# untitled.net
KiCad netlist of a schematic drawn in EAGLE
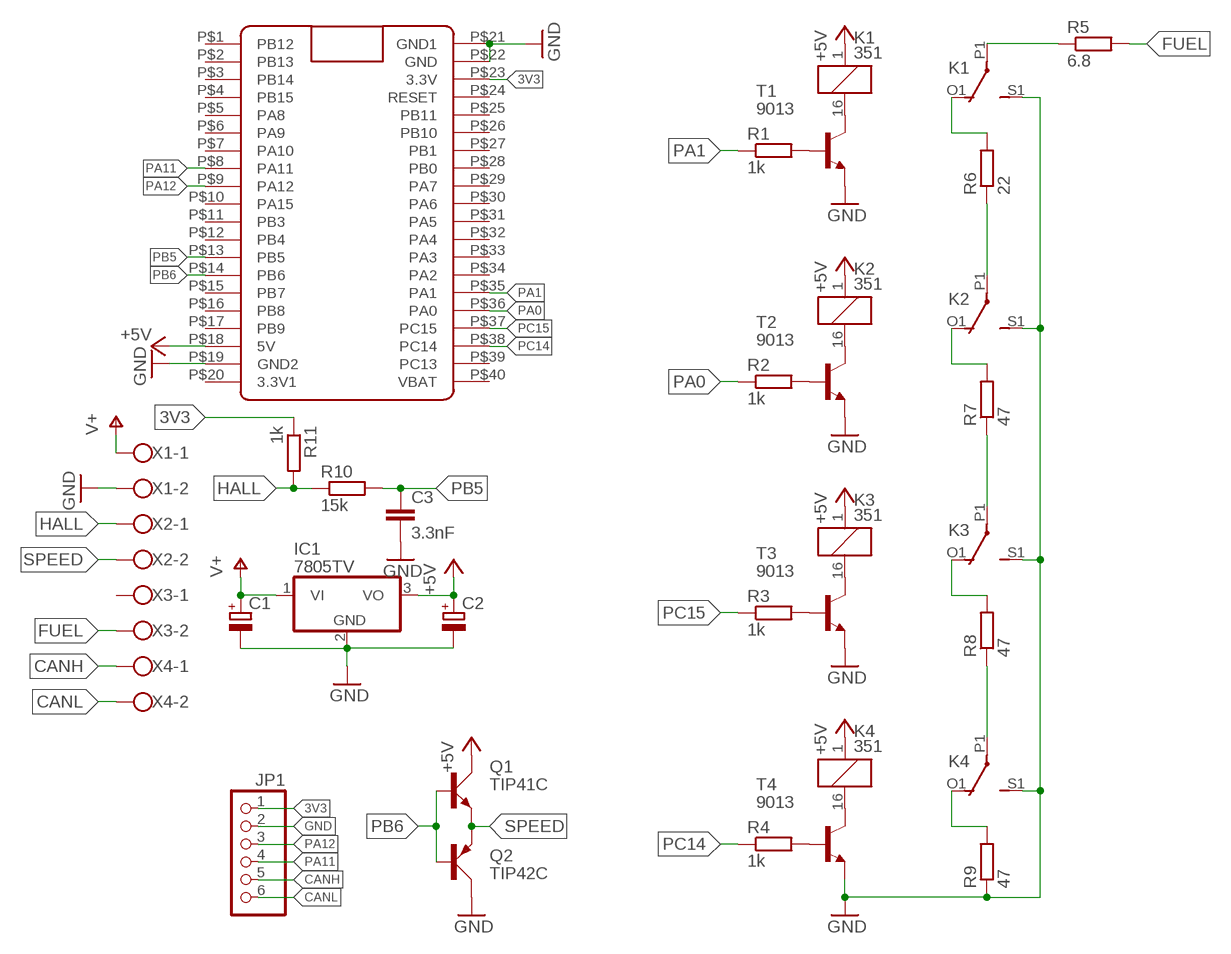
[diagram p0: schematic, sheet 1]

(export (version "E")
  (design (tool "Eeschema 10.0.6"))
  (components
    (comp (ref "C1")
      (value "CPOL-EUE5-10.5")
      (footprint "eagle-import:E5-10,5")
      (libsource (lib "eagle-import") (part "CPOL-EUE5-10.5"))
    )
    (comp (ref "C2")
      (value "CPOL-EUE5-10.5")
      (footprint "eagle-import:E5-10,5")
      (libsource (lib "eagle-import") (part "CPOL-EUE5-10.5"))
    )
    (comp (ref "C3")
      (value "3.3nF")
      (footprint "eagle-import:C050-024X044")
      (libsource (lib "eagle-import") (part "C-EU050-024X044"))
    )
    (comp (ref "IC1")
      (value "7805TV")
      (footprint "eagle-import:TO220V")
      (libsource (lib "eagle-import") (part "78TV05"))
    )
    (comp (ref "JP1")
      (value "PINHD-1X6")
      (footprint "eagle-import:1X06")
      (libsource (lib "eagle-import") (part "PINHD-1X6"))
    )
    (comp (ref "K1")
      (value "351")
      (footprint "eagle-import:351")
      (libsource (lib "eagle-import") (part "351"))
    )
    (comp (ref "K2")
      (value "351")
      (footprint "eagle-import:351")
      (libsource (lib "eagle-import") (part "351"))
    )
    (comp (ref "K3")
      (value "351")
      (footprint "eagle-import:351")
      (libsource (lib "eagle-import") (part "351"))
    )
    (comp (ref "K4")
      (value "351")
      (footprint "eagle-import:351")
      (libsource (lib "eagle-import") (part "351"))
    )
    (comp (ref "Q1")
      (value "TIP41C")
      (footprint "eagle-import:TO220AV")
      (libsource (lib "eagle-import") (part "TIP41C"))
    )
    (comp (ref "Q2")
      (value "TIP42C")
      (footprint "eagle-import:TO220AV")
      (libsource (lib "eagle-import") (part "TIP42C"))
    )
    (comp (ref "R1")
      (value "1k")
      (footprint "eagle-import:0207_7")
      (libsource (lib "eagle-import") (part "R-EU_0207/7"))
    )
    (comp (ref "R2")
      (value "1k")
      (footprint "eagle-import:0207_7")
      (libsource (lib "eagle-import") (part "R-EU_0207/7"))
    )
    (comp (ref "R3")
      (value "1k")
      (footprint "eagle-import:0207_7")
      (libsource (lib "eagle-import") (part "R-EU_0207/7"))
    )
    (comp (ref "R4")
      (value "1k")
      (footprint "eagle-import:0207_7")
      (libsource (lib "eagle-import") (part "R-EU_0207/7"))
    )
    (comp (ref "R5")
      (value "6.8")
      (footprint "eagle-import:0207_7")
      (libsource (lib "eagle-import") (part "R-EU_0207/7"))
    )
    (comp (ref "R6")
      (value "22")
      (footprint "eagle-import:0207_7")
      (libsource (lib "eagle-import") (part "R-EU_0207/7"))
    )
    (comp (ref "R7")
      (value "47")
      (footprint "eagle-import:0207_7")
      (libsource (lib "eagle-import") (part "R-EU_0207/7"))
    )
    (comp (ref "R8")
      (value "47")
      (footprint "eagle-import:0207_7")
      (libsource (lib "eagle-import") (part "R-EU_0207/7"))
    )
    (comp (ref "R9")
      (value "47")
      (footprint "eagle-import:0207_7")
      (libsource (lib "eagle-import") (part "R-EU_0207/7"))
    )
    (comp (ref "R10")
      (value "15k")
      (footprint "eagle-import:0207_7")
      (libsource (lib "eagle-import") (part "R-EU_0207/7"))
    )
    (comp (ref "R11")
      (value "1k")
      (footprint "eagle-import:0207_7")
      (libsource (lib "eagle-import") (part "R-EU_0207/7"))
    )
    (comp (ref "T1")
      (value "9013")
      (footprint "eagle-import:TO92-EBC")
      (libsource (lib "eagle-import") (part "-NPN-TO92-EBC"))
    )
    (comp (ref "T2")
      (value "9013")
      (footprint "eagle-import:TO92-EBC")
      (libsource (lib "eagle-import") (part "-NPN-TO92-EBC"))
    )
    (comp (ref "T3")
      (value "9013")
      (footprint "eagle-import:TO92-EBC")
      (libsource (lib "eagle-import") (part "-NPN-TO92-EBC"))
    )
    (comp (ref "T4")
      (value "9013")
      (footprint "eagle-import:TO92-EBC")
      (libsource (lib "eagle-import") (part "-NPN-TO92-EBC"))
    )
    (comp (ref "U$1")
      (value "BLUE_PILL")
      (footprint "eagle-import:BLUE_PILL")
      (libsource (lib "eagle-import") (part "BLUE_PILL"))
    )
    (comp (ref "X1")
      (value "W237-102")
      (footprint "eagle-import:W237-102")
      (fields (field (name "MPN") "237-102"))
      (libsource (lib "eagle-import") (part "W237-102"))
    )
    (comp (ref "X2")
      (value "W237-102")
      (footprint "eagle-import:W237-102")
      (fields (field (name "MPN") "237-102"))
      (libsource (lib "eagle-import") (part "W237-102"))
    )
    (comp (ref "X3")
      (value "W237-102")
      (footprint "eagle-import:W237-102")
      (fields (field (name "MPN") "237-102"))
      (libsource (lib "eagle-import") (part "W237-102"))
    )
    (comp (ref "X4")
      (value "W237-102")
      (footprint "eagle-import:W237-102")
      (fields (field (name "MPN") "237-102"))
      (libsource (lib "eagle-import") (part "W237-102"))
    )
  )
  (nets
    (net (code "1") (name "+5V") (class "Default")
      (node (ref "C2") (pin "+") (pinfunction "+_+") (pintype "passive"))
      (node (ref "IC1") (pin "3") (pinfunction "VO_3") (pintype "passive"))
      (node (ref "K1") (pin "1") (pinfunction "1_1") (pintype "passive"))
      (node (ref "K2") (pin "1") (pinfunction "1_1") (pintype "passive"))
      (node (ref "K3") (pin "1") (pinfunction "1_1") (pintype "passive"))
      (node (ref "K4") (pin "1") (pinfunction "1_1") (pintype "passive"))
      (node (ref "Q1") (pin "C") (pinfunction "C_C") (pintype "passive"))
      (node (ref "U$1") (pin "P$18") (pinfunction "5V_P$18") (pintype "bidirectional"))
    )
    (net (code "2") (name "3V3") (class "Default")
      (node (ref "JP1") (pin "1") (pinfunction "1_1") (pintype "passive"))
      (node (ref "R11") (pin "1") (pinfunction "1_1") (pintype "passive"))
      (node (ref "U$1") (pin "P$23") (pinfunction "3.3V_P$23") (pintype "bidirectional"))
    )
    (net (code "3") (name "CANH") (class "Default")
      (node (ref "JP1") (pin "5") (pinfunction "5_5") (pintype "passive"))
      (node (ref "X4") (pin "1") (pinfunction "KL_1") (pintype "passive"))
    )
    (net (code "4") (name "CANL") (class "Default")
      (node (ref "JP1") (pin "6") (pinfunction "6_6") (pintype "passive"))
      (node (ref "X4") (pin "2") (pinfunction "KL_2") (pintype "passive"))
    )
    (net (code "5") (name "FUEL") (class "Default")
      (node (ref "R5") (pin "2") (pinfunction "2_2") (pintype "passive"))
      (node (ref "X3") (pin "2") (pinfunction "KL_2") (pintype "passive"))
    )
    (net (code "6") (name "GND") (class "Default")
      (node (ref "C1") (pin "-") (pinfunction "-_-") (pintype "passive"))
      (node (ref "C2") (pin "-") (pinfunction "-_-") (pintype "passive"))
      (node (ref "C3") (pin "2") (pinfunction "2_2") (pintype "passive"))
      (node (ref "IC1") (pin "2") (pinfunction "GND_2") (pintype "passive"))
      (node (ref "JP1") (pin "2") (pinfunction "2_2") (pintype "passive"))
      (node (ref "K1") (pin "S1") (pinfunction "S_S1") (pintype "passive"))
      (node (ref "K2") (pin "S1") (pinfunction "S_S1") (pintype "passive"))
      (node (ref "K3") (pin "S1") (pinfunction "S_S1") (pintype "passive"))
      (node (ref "K4") (pin "S1") (pinfunction "S_S1") (pintype "passive"))
      (node (ref "Q2") (pin "C") (pinfunction "C_C") (pintype "passive"))
      (node (ref "R9") (pin "1") (pinfunction "1_1") (pintype "passive"))
      (node (ref "T1") (pin "E") (pinfunction "E_E") (pintype "passive"))
      (node (ref "T2") (pin "E") (pinfunction "E_E") (pintype "passive"))
      (node (ref "T3") (pin "E") (pinfunction "E_E") (pintype "passive"))
      (node (ref "T4") (pin "E") (pinfunction "E_E") (pintype "passive"))
      (node (ref "U$1") (pin "P$19") (pinfunction "GND2_P$19") (pintype "bidirectional"))
      (node (ref "U$1") (pin "P$21") (pinfunction "GND1_P$21") (pintype "power_in"))
      (node (ref "U$1") (pin "P$22") (pinfunction "GND_P$22") (pintype "bidirectional"))
      (node (ref "X1") (pin "2") (pinfunction "KL_2") (pintype "passive"))
    )
    (net (code "7") (name "HALL") (class "Default")
      (node (ref "R10") (pin "1") (pinfunction "1_1") (pintype "passive"))
      (node (ref "R11") (pin "2") (pinfunction "2_2") (pintype "passive"))
      (node (ref "X2") (pin "1") (pinfunction "KL_1") (pintype "passive"))
    )
    (net (code "8") (name "Net-(K1A-2)") (class "Default")
      (node (ref "K1") (pin "16") (pinfunction "2_16") (pintype "passive"))
      (node (ref "T1") (pin "C") (pinfunction "C_C") (pintype "passive"))
    )
    (net (code "9") (name "Net-(K1B-O)") (class "Default")
      (node (ref "K1") (pin "O1") (pinfunction "O_O1") (pintype "passive"))
      (node (ref "R6") (pin "2") (pinfunction "2_2") (pintype "passive"))
    )
    (net (code "10") (name "Net-(K1B-P)") (class "Default")
      (node (ref "K1") (pin "P1") (pinfunction "P_P1") (pintype "passive"))
      (node (ref "R5") (pin "1") (pinfunction "1_1") (pintype "passive"))
    )
    (net (code "11") (name "Net-(K2A-2)") (class "Default")
      (node (ref "K2") (pin "16") (pinfunction "2_16") (pintype "passive"))
      (node (ref "T2") (pin "C") (pinfunction "C_C") (pintype "passive"))
    )
    (net (code "12") (name "Net-(K2B-O)") (class "Default")
      (node (ref "K2") (pin "O1") (pinfunction "O_O1") (pintype "passive"))
      (node (ref "R7") (pin "2") (pinfunction "2_2") (pintype "passive"))
    )
    (net (code "13") (name "Net-(K2B-P)") (class "Default")
      (node (ref "K2") (pin "P1") (pinfunction "P_P1") (pintype "passive"))
      (node (ref "R6") (pin "1") (pinfunction "1_1") (pintype "passive"))
    )
    (net (code "14") (name "Net-(K3A-2)") (class "Default")
      (node (ref "K3") (pin "16") (pinfunction "2_16") (pintype "passive"))
      (node (ref "T3") (pin "C") (pinfunction "C_C") (pintype "passive"))
    )
    (net (code "15") (name "Net-(K3B-O)") (class "Default")
      (node (ref "K3") (pin "O1") (pinfunction "O_O1") (pintype "passive"))
      (node (ref "R8") (pin "2") (pinfunction "2_2") (pintype "passive"))
    )
    (net (code "16") (name "Net-(K3B-P)") (class "Default")
      (node (ref "K3") (pin "P1") (pinfunction "P_P1") (pintype "passive"))
      (node (ref "R7") (pin "1") (pinfunction "1_1") (pintype "passive"))
    )
    (net (code "17") (name "Net-(K4A-2)") (class "Default")
      (node (ref "K4") (pin "16") (pinfunction "2_16") (pintype "passive"))
      (node (ref "T4") (pin "C") (pinfunction "C_C") (pintype "passive"))
    )
    (net (code "18") (name "Net-(K4B-O)") (class "Default")
      (node (ref "K4") (pin "O1") (pinfunction "O_O1") (pintype "passive"))
      (node (ref "R9") (pin "2") (pinfunction "2_2") (pintype "passive"))
    )
    (net (code "19") (name "Net-(K4B-P)") (class "Default")
      (node (ref "K4") (pin "P1") (pinfunction "P_P1") (pintype "passive"))
      (node (ref "R8") (pin "1") (pinfunction "1_1") (pintype "passive"))
    )
    (net (code "20") (name "Net-(R1-Pad2)") (class "Default")
      (node (ref "R1") (pin "2") (pinfunction "2_2") (pintype "passive"))
      (node (ref "T1") (pin "B") (pinfunction "B_B") (pintype "passive"))
    )
    (net (code "21") (name "Net-(R2-Pad2)") (class "Default")
      (node (ref "R2") (pin "2") (pinfunction "2_2") (pintype "passive"))
      (node (ref "T2") (pin "B") (pinfunction "B_B") (pintype "passive"))
    )
    (net (code "22") (name "Net-(R3-Pad2)") (class "Default")
      (node (ref "R3") (pin "2") (pinfunction "2_2") (pintype "passive"))
      (node (ref "T3") (pin "B") (pinfunction "B_B") (pintype "passive"))
    )
    (net (code "23") (name "Net-(R4-Pad2)") (class "Default")
      (node (ref "R4") (pin "2") (pinfunction "2_2") (pintype "passive"))
      (node (ref "T4") (pin "B") (pinfunction "B_B") (pintype "passive"))
    )
    (net (code "24") (name "PA0") (class "Default")
      (node (ref "R2") (pin "1") (pinfunction "1_1") (pintype "passive"))
      (node (ref "U$1") (pin "P$36") (pinfunction "PA0_P$36") (pintype "bidirectional"))
    )
    (net (code "25") (name "PA1") (class "Default")
      (node (ref "R1") (pin "1") (pinfunction "1_1") (pintype "passive"))
      (node (ref "U$1") (pin "P$35") (pinfunction "PA1_P$35") (pintype "bidirectional"))
    )
    (net (code "26") (name "PA11") (class "Default")
      (node (ref "JP1") (pin "4") (pinfunction "4_4") (pintype "passive"))
      (node (ref "U$1") (pin "P$8") (pinfunction "PA11_P$8") (pintype "bidirectional"))
    )
    (net (code "27") (name "PA12") (class "Default")
      (node (ref "JP1") (pin "3") (pinfunction "3_3") (pintype "passive"))
      (node (ref "U$1") (pin "P$9") (pinfunction "PA12_P$9") (pintype "bidirectional"))
    )
    (net (code "28") (name "PB5") (class "Default")
      (node (ref "C3") (pin "1") (pinfunction "1_1") (pintype "passive"))
      (node (ref "R10") (pin "2") (pinfunction "2_2") (pintype "passive"))
      (node (ref "U$1") (pin "P$13") (pinfunction "PB5_P$13") (pintype "bidirectional"))
    )
    (net (code "29") (name "PB6") (class "Default")
      (node (ref "Q1") (pin "B") (pinfunction "B_B") (pintype "passive"))
      (node (ref "Q2") (pin "B") (pinfunction "B_B") (pintype "passive"))
      (node (ref "U$1") (pin "P$14") (pinfunction "PB6_P$14") (pintype "bidirectional"))
    )
    (net (code "30") (name "PC14") (class "Default")
      (node (ref "R4") (pin "1") (pinfunction "1_1") (pintype "passive"))
      (node (ref "U$1") (pin "P$38") (pinfunction "PC14_P$38") (pintype "bidirectional"))
    )
    (net (code "31") (name "PC15") (class "Default")
      (node (ref "R3") (pin "1") (pinfunction "1_1") (pintype "passive"))
      (node (ref "U$1") (pin "P$37") (pinfunction "PC15_P$37") (pintype "bidirectional"))
    )
    (net (code "32") (name "SPEED") (class "Default")
      (node (ref "Q1") (pin "E") (pinfunction "E_E") (pintype "passive"))
      (node (ref "Q2") (pin "E") (pinfunction "E_E") (pintype "passive"))
      (node (ref "X2") (pin "2") (pinfunction "KL_2") (pintype "passive"))
    )
    (net (code "33") (name "V+") (class "Default")
      (node (ref "C1") (pin "+") (pinfunction "+_+") (pintype "passive"))
      (node (ref "IC1") (pin "1") (pinfunction "VI_1") (pintype "input"))
      (node (ref "X1") (pin "1") (pinfunction "KL_1") (pintype "passive"))
    )
    (net (code "34") (name "unconnected-(U$1-3.3V1-PadP$20)") (class "Default")
      (node (ref "U$1") (pin "P$20") (pinfunction "3.3V1_P$20") (pintype "bidirectional"))
    )
    (net (code "35") (name "unconnected-(U$1-PA2-PadP$34)") (class "Default")
      (node (ref "U$1") (pin "P$34") (pinfunction "PA2_P$34") (pintype "bidirectional"))
    )
    (net (code "36") (name "unconnected-(U$1-PA3-PadP$33)") (class "Default")
      (node (ref "U$1") (pin "P$33") (pinfunction "PA3_P$33") (pintype "bidirectional"))
    )
    (net (code "37") (name "unconnected-(U$1-PA4-PadP$32)") (class "Default")
      (node (ref "U$1") (pin "P$32") (pinfunction "PA4_P$32") (pintype "bidirectional"))
    )
    (net (code "38") (name "unconnected-(U$1-PA5-PadP$31)") (class "Default")
      (node (ref "U$1") (pin "P$31") (pinfunction "PA5_P$31") (pintype "bidirectional"))
    )
    (net (code "39") (name "unconnected-(U$1-PA6-PadP$30)") (class "Default")
      (node (ref "U$1") (pin "P$30") (pinfunction "PA6_P$30") (pintype "bidirectional"))
    )
    (net (code "40") (name "unconnected-(U$1-PA7-PadP$29)") (class "Default")
      (node (ref "U$1") (pin "P$29") (pinfunction "PA7_P$29") (pintype "bidirectional"))
    )
    (net (code "41") (name "unconnected-(U$1-PA8-PadP$5)") (class "Default")
      (node (ref "U$1") (pin "P$5") (pinfunction "PA8_P$5") (pintype "bidirectional"))
    )
    (net (code "42") (name "unconnected-(U$1-PA9-PadP$6)") (class "Default")
      (node (ref "U$1") (pin "P$6") (pinfunction "PA9_P$6") (pintype "bidirectional"))
    )
    (net (code "43") (name "unconnected-(U$1-PA10-PadP$7)") (class "Default")
      (node (ref "U$1") (pin "P$7") (pinfunction "PA10_P$7") (pintype "bidirectional"))
    )
    (net (code "44") (name "unconnected-(U$1-PA15-PadP$10)") (class "Default")
      (node (ref "U$1") (pin "P$10") (pinfunction "PA15_P$10") (pintype "bidirectional"))
    )
    (net (code "45") (name "unconnected-(U$1-PB0-PadP$28)") (class "Default")
      (node (ref "U$1") (pin "P$28") (pinfunction "PB0_P$28") (pintype "bidirectional"))
    )
    (net (code "46") (name "unconnected-(U$1-PB1-PadP$27)") (class "Default")
      (node (ref "U$1") (pin "P$27") (pinfunction "PB1_P$27") (pintype "bidirectional"))
    )
    (net (code "47") (name "unconnected-(U$1-PB3-PadP$11)") (class "Default")
      (node (ref "U$1") (pin "P$11") (pinfunction "PB3_P$11") (pintype "bidirectional"))
    )
    (net (code "48") (name "unconnected-(U$1-PB4-PadP$12)") (class "Default")
      (node (ref "U$1") (pin "P$12") (pinfunction "PB4_P$12") (pintype "bidirectional"))
    )
    (net (code "49") (name "unconnected-(U$1-PB7-PadP$15)") (class "Default")
      (node (ref "U$1") (pin "P$15") (pinfunction "PB7_P$15") (pintype "bidirectional"))
    )
    (net (code "50") (name "unconnected-(U$1-PB8-PadP$16)") (class "Default")
      (node (ref "U$1") (pin "P$16") (pinfunction "PB8_P$16") (pintype "bidirectional"))
    )
    (net (code "51") (name "unconnected-(U$1-PB9-PadP$17)") (class "Default")
      (node (ref "U$1") (pin "P$17") (pinfunction "PB9_P$17") (pintype "bidirectional"))
    )
    (net (code "52") (name "unconnected-(U$1-PB10-PadP$26)") (class "Default")
      (node (ref "U$1") (pin "P$26") (pinfunction "PB10_P$26") (pintype "bidirectional"))
    )
    (net (code "53") (name "unconnected-(U$1-PB11-PadP$25)") (class "Default")
      (node (ref "U$1") (pin "P$25") (pinfunction "PB11_P$25") (pintype "bidirectional"))
    )
    (net (code "54") (name "unconnected-(U$1-PB12-PadP$1)") (class "Default")
      (node (ref "U$1") (pin "P$1") (pinfunction "PB12_P$1") (pintype "bidirectional"))
    )
    (net (code "55") (name "unconnected-(U$1-PB13-PadP$2)") (class "Default")
      (node (ref "U$1") (pin "P$2") (pinfunction "PB13_P$2") (pintype "bidirectional"))
    )
    (net (code "56") (name "unconnected-(U$1-PB14-PadP$3)") (class "Default")
      (node (ref "U$1") (pin "P$3") (pinfunction "PB14_P$3") (pintype "bidirectional"))
    )
    (net (code "57") (name "unconnected-(U$1-PB15-PadP$4)") (class "Default")
      (node (ref "U$1") (pin "P$4") (pinfunction "PB15_P$4") (pintype "bidirectional"))
    )
    (net (code "58") (name "unconnected-(U$1-PC13-PadP$39)") (class "Default")
      (node (ref "U$1") (pin "P$39") (pinfunction "PC13_P$39") (pintype "bidirectional"))
    )
    (net (code "59") (name "unconnected-(U$1-RESET-PadP$24)") (class "Default")
      (node (ref "U$1") (pin "P$24") (pinfunction "RESET_P$24") (pintype "bidirectional"))
    )
    (net (code "60") (name "unconnected-(U$1-VBAT-PadP$40)") (class "Default")
      (node (ref "U$1") (pin "P$40") (pinfunction "VBAT_P$40") (pintype "bidirectional"))
    )
    (net (code "61") (name "unconnected-(X3A-KL-Pad1)") (class "Default")
      (node (ref "X3") (pin "1") (pinfunction "KL_1") (pintype "passive"))
    )
  )
)
